# 2_cyber60-2-matrix.net
KiCad netlist of a schematic drawn in Altium Designer
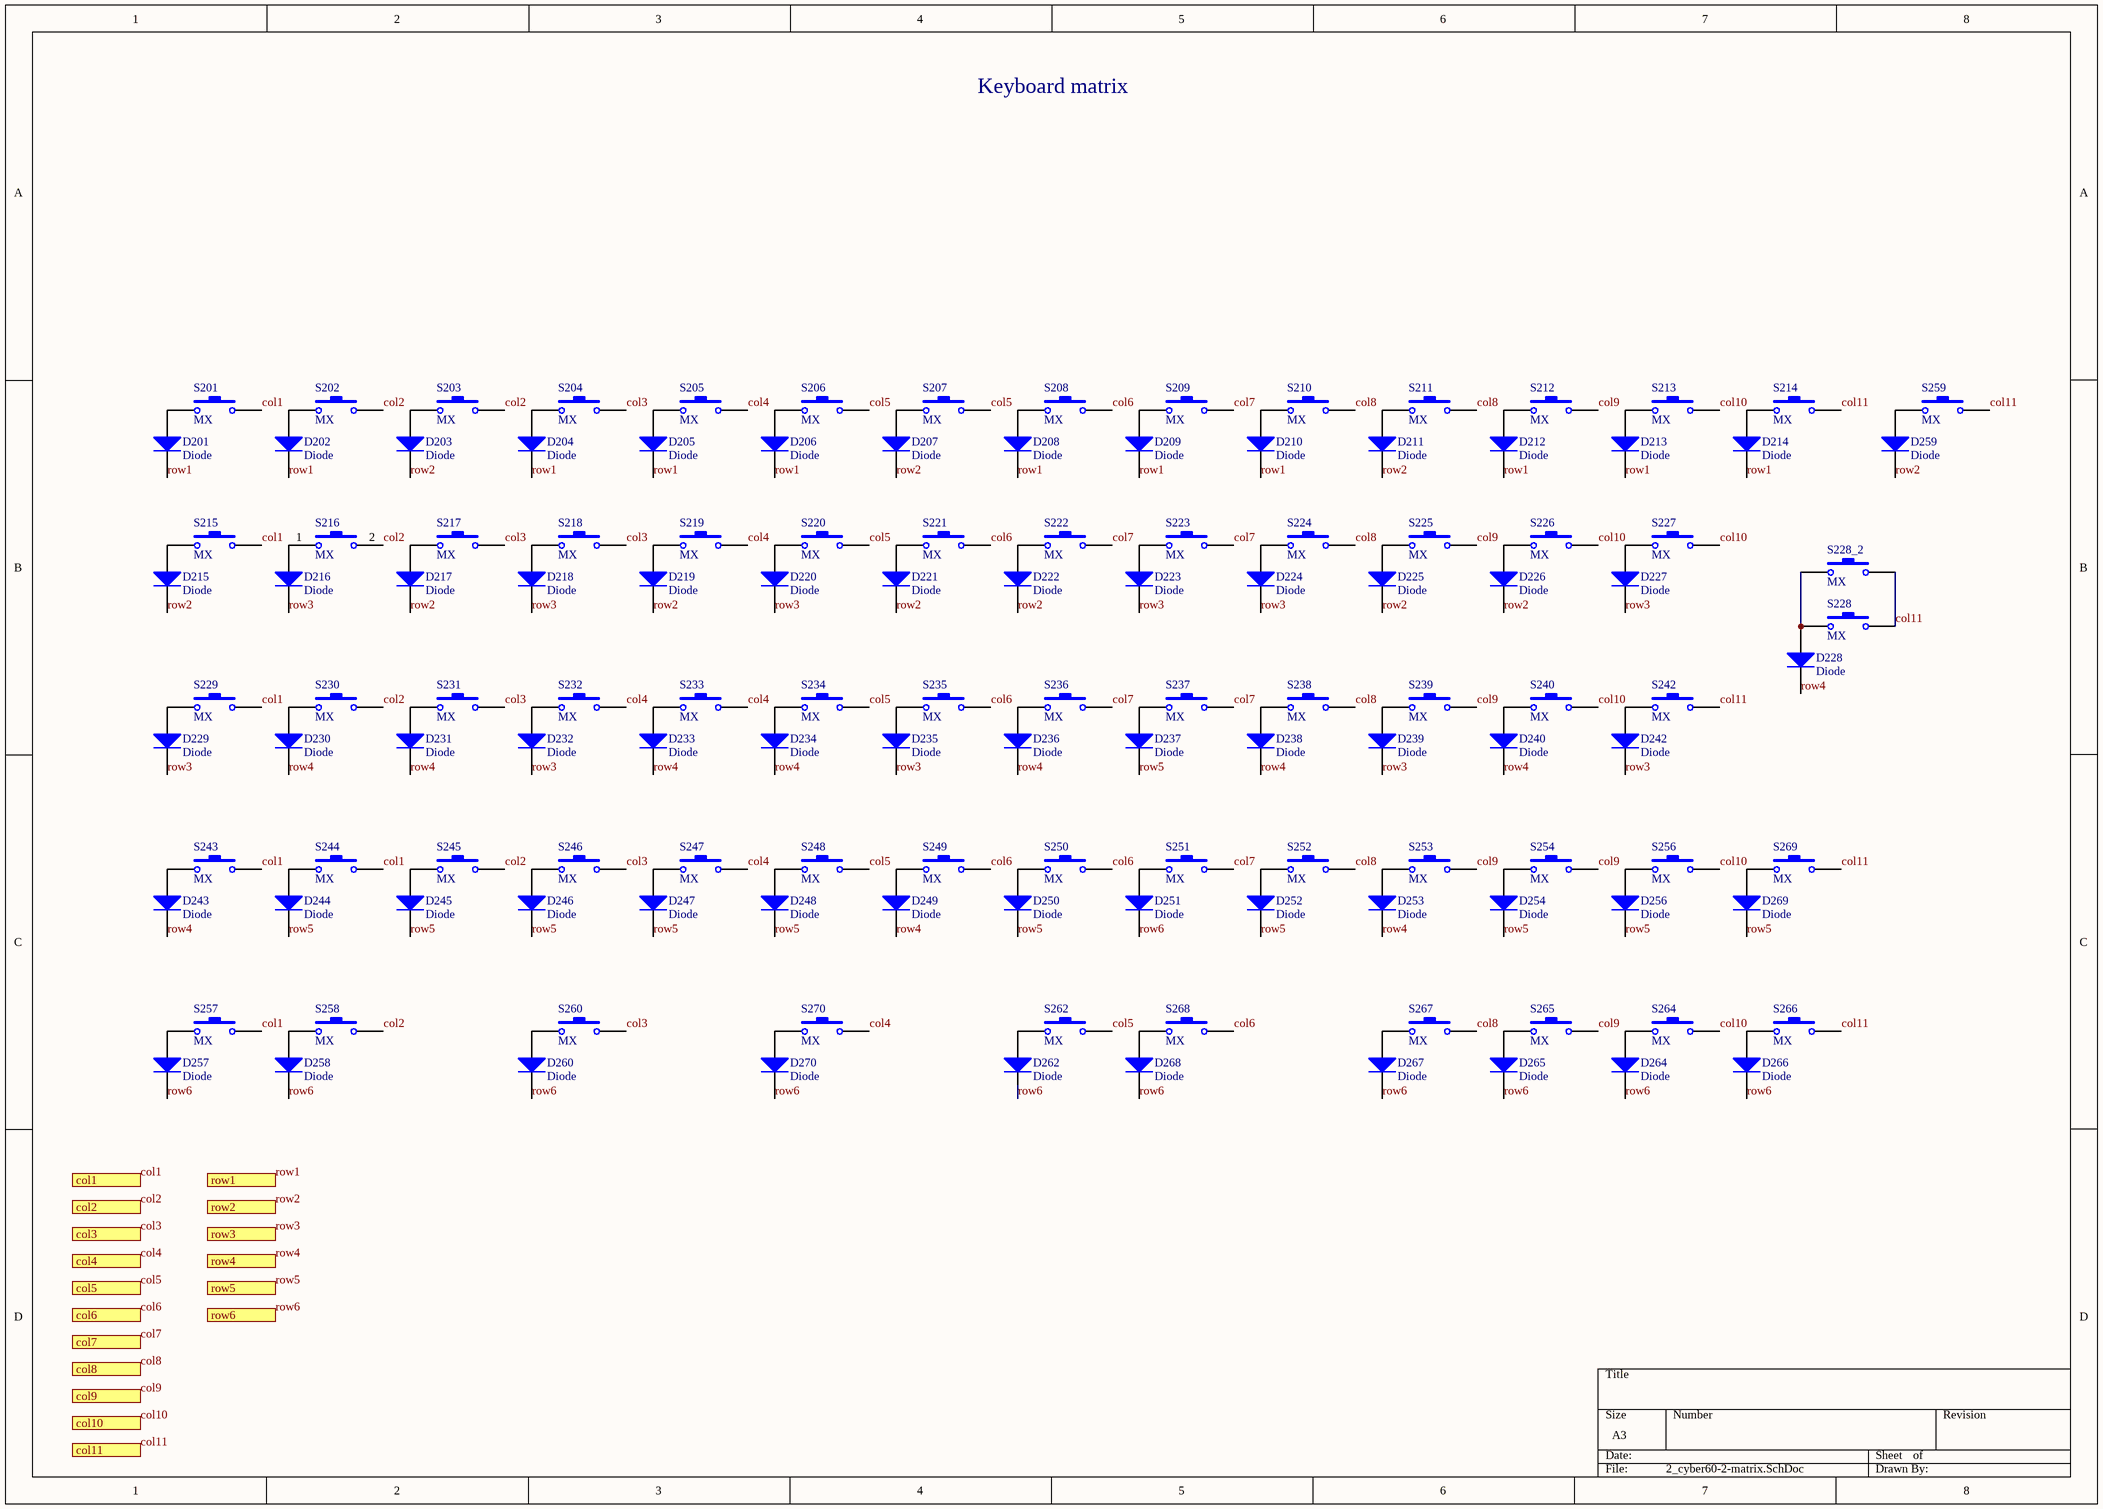
[diagram p0: 2_cyber60-2-matrix.SchDoc]

(export (version "E")
  (design (tool "Eeschema 10.0.6"))
  (components
    (comp (ref "D201")
      (value "Diode")
      (footprint "SOD-123")
      (description "Default Diode")
      (fields (field (name "LCSC PART #") "C81598") (field (name "MRF.PART") "1N4148W"))
      (libsource (lib "Miscellaneous Devices") (part "Diode"))
    )
    (comp (ref "D202")
      (value "Diode")
      (footprint "SOD-123")
      (description "Default Diode")
      (fields (field (name "LCSC PART #") "C81598") (field (name "MRF.PART") "1N4148W"))
      (libsource (lib "Miscellaneous Devices") (part "Diode"))
    )
    (comp (ref "D203")
      (value "Diode")
      (footprint "SOD-123")
      (description "Default Diode")
      (fields (field (name "LCSC PART #") "C81598") (field (name "MRF.PART") "1N4148W"))
      (libsource (lib "Miscellaneous Devices") (part "Diode"))
    )
    (comp (ref "D204")
      (value "Diode")
      (footprint "SOD-123")
      (description "Default Diode")
      (fields (field (name "LCSC PART #") "C81598") (field (name "MRF.PART") "1N4148W"))
      (libsource (lib "Miscellaneous Devices") (part "Diode"))
    )
    (comp (ref "D205")
      (value "Diode")
      (footprint "SOD-123")
      (description "Default Diode")
      (fields (field (name "LCSC PART #") "C81598") (field (name "MRF.PART") "1N4148W"))
      (libsource (lib "Miscellaneous Devices") (part "Diode"))
    )
    (comp (ref "D206")
      (value "Diode")
      (footprint "SOD-123")
      (description "Default Diode")
      (fields (field (name "LCSC PART #") "C81598") (field (name "MRF.PART") "1N4148W"))
      (libsource (lib "Miscellaneous Devices") (part "Diode"))
    )
    (comp (ref "D207")
      (value "Diode")
      (footprint "SOD-123")
      (description "Default Diode")
      (fields (field (name "LCSC PART #") "C81598") (field (name "MRF.PART") "1N4148W"))
      (libsource (lib "Miscellaneous Devices") (part "Diode"))
    )
    (comp (ref "D208")
      (value "Diode")
      (footprint "SOD-123")
      (description "Default Diode")
      (fields (field (name "LCSC PART #") "C81598") (field (name "MRF.PART") "1N4148W"))
      (libsource (lib "Miscellaneous Devices") (part "Diode"))
    )
    (comp (ref "D209")
      (value "Diode")
      (footprint "SOD-123")
      (description "Default Diode")
      (fields (field (name "LCSC PART #") "C81598") (field (name "MRF.PART") "1N4148W"))
      (libsource (lib "Miscellaneous Devices") (part "Diode"))
    )
    (comp (ref "D210")
      (value "Diode")
      (footprint "SOD-123")
      (description "Default Diode")
      (fields (field (name "LCSC PART #") "C81598") (field (name "MRF.PART") "1N4148W"))
      (libsource (lib "Miscellaneous Devices") (part "Diode"))
    )
    (comp (ref "D211")
      (value "Diode")
      (footprint "SOD-123")
      (description "Default Diode")
      (fields (field (name "LCSC PART #") "C81598") (field (name "MRF.PART") "1N4148W"))
      (libsource (lib "Miscellaneous Devices") (part "Diode"))
    )
    (comp (ref "D212")
      (value "Diode")
      (footprint "SOD-123")
      (description "Default Diode")
      (fields (field (name "LCSC PART #") "C81598") (field (name "MRF.PART") "1N4148W"))
      (libsource (lib "Miscellaneous Devices") (part "Diode"))
    )
    (comp (ref "D213")
      (value "Diode")
      (footprint "SOD-123")
      (description "Default Diode")
      (fields (field (name "LCSC PART #") "C81598") (field (name "MRF.PART") "1N4148W"))
      (libsource (lib "Miscellaneous Devices") (part "Diode"))
    )
    (comp (ref "D214")
      (value "Diode")
      (footprint "SOD-123")
      (description "Default Diode")
      (fields (field (name "LCSC PART #") "C81598") (field (name "MRF.PART") "1N4148W"))
      (libsource (lib "Miscellaneous Devices") (part "Diode"))
    )
    (comp (ref "D215")
      (value "Diode")
      (footprint "SOD-123")
      (description "Default Diode")
      (fields (field (name "LCSC PART #") "C81598") (field (name "MRF.PART") "1N4148W"))
      (libsource (lib "Miscellaneous Devices") (part "Diode"))
    )
    (comp (ref "D216")
      (value "Diode")
      (footprint "SOD-123")
      (description "Default Diode")
      (fields (field (name "LCSC PART #") "C81598") (field (name "MRF.PART") "1N4148W"))
      (libsource (lib "Miscellaneous Devices") (part "Diode"))
    )
    (comp (ref "D217")
      (value "Diode")
      (footprint "SOD-123")
      (description "Default Diode")
      (fields (field (name "LCSC PART #") "C81598") (field (name "MRF.PART") "1N4148W"))
      (libsource (lib "Miscellaneous Devices") (part "Diode"))
    )
    (comp (ref "D218")
      (value "Diode")
      (footprint "SOD-123")
      (description "Default Diode")
      (fields (field (name "LCSC PART #") "C81598") (field (name "MRF.PART") "1N4148W"))
      (libsource (lib "Miscellaneous Devices") (part "Diode"))
    )
    (comp (ref "D219")
      (value "Diode")
      (footprint "SOD-123")
      (description "Default Diode")
      (fields (field (name "LCSC PART #") "C81598") (field (name "MRF.PART") "1N4148W"))
      (libsource (lib "Miscellaneous Devices") (part "Diode"))
    )
    (comp (ref "D220")
      (value "Diode")
      (footprint "SOD-123")
      (description "Default Diode")
      (fields (field (name "LCSC PART #") "C81598") (field (name "MRF.PART") "1N4148W"))
      (libsource (lib "Miscellaneous Devices") (part "Diode"))
    )
    (comp (ref "D221")
      (value "Diode")
      (footprint "SOD-123")
      (description "Default Diode")
      (fields (field (name "LCSC PART #") "C81598") (field (name "MRF.PART") "1N4148W"))
      (libsource (lib "Miscellaneous Devices") (part "Diode"))
    )
    (comp (ref "D222")
      (value "Diode")
      (footprint "SOD-123")
      (description "Default Diode")
      (fields (field (name "LCSC PART #") "C81598") (field (name "MRF.PART") "1N4148W"))
      (libsource (lib "Miscellaneous Devices") (part "Diode"))
    )
    (comp (ref "D223")
      (value "Diode")
      (footprint "SOD-123")
      (description "Default Diode")
      (fields (field (name "LCSC PART #") "C81598") (field (name "MRF.PART") "1N4148W"))
      (libsource (lib "Miscellaneous Devices") (part "Diode"))
    )
    (comp (ref "D224")
      (value "Diode")
      (footprint "SOD-123")
      (description "Default Diode")
      (fields (field (name "LCSC PART #") "C81598") (field (name "MRF.PART") "1N4148W"))
      (libsource (lib "Miscellaneous Devices") (part "Diode"))
    )
    (comp (ref "D225")
      (value "Diode")
      (footprint "SOD-123")
      (description "Default Diode")
      (fields (field (name "LCSC PART #") "C81598") (field (name "MRF.PART") "1N4148W"))
      (libsource (lib "Miscellaneous Devices") (part "Diode"))
    )
    (comp (ref "D226")
      (value "Diode")
      (footprint "SOD-123")
      (description "Default Diode")
      (fields (field (name "LCSC PART #") "C81598") (field (name "MRF.PART") "1N4148W"))
      (libsource (lib "Miscellaneous Devices") (part "Diode"))
    )
    (comp (ref "D227")
      (value "Diode")
      (footprint "SOD-123")
      (description "Default Diode")
      (fields (field (name "LCSC PART #") "C81598") (field (name "MRF.PART") "1N4148W"))
      (libsource (lib "Miscellaneous Devices") (part "Diode"))
    )
    (comp (ref "D228")
      (value "Diode")
      (footprint "SOD-123")
      (description "Default Diode")
      (fields (field (name "LCSC PART #") "C81598") (field (name "MRF.PART") "1N4148W"))
      (libsource (lib "Miscellaneous Devices") (part "Diode"))
    )
    (comp (ref "D229")
      (value "Diode")
      (footprint "SOD-123")
      (description "Default Diode")
      (fields (field (name "LCSC PART #") "C81598") (field (name "MRF.PART") "1N4148W"))
      (libsource (lib "Miscellaneous Devices") (part "Diode"))
    )
    (comp (ref "D230")
      (value "Diode")
      (footprint "SOD-123")
      (description "Default Diode")
      (fields (field (name "LCSC PART #") "C81598") (field (name "MRF.PART") "1N4148W"))
      (libsource (lib "Miscellaneous Devices") (part "Diode"))
    )
    (comp (ref "D231")
      (value "Diode")
      (footprint "SOD-123")
      (description "Default Diode")
      (fields (field (name "LCSC PART #") "C81598") (field (name "MRF.PART") "1N4148W"))
      (libsource (lib "Miscellaneous Devices") (part "Diode"))
    )
    (comp (ref "D232")
      (value "Diode")
      (footprint "SOD-123")
      (description "Default Diode")
      (fields (field (name "LCSC PART #") "C81598") (field (name "MRF.PART") "1N4148W"))
      (libsource (lib "Miscellaneous Devices") (part "Diode"))
    )
    (comp (ref "D233")
      (value "Diode")
      (footprint "SOD-123")
      (description "Default Diode")
      (fields (field (name "LCSC PART #") "C81598") (field (name "MRF.PART") "1N4148W"))
      (libsource (lib "Miscellaneous Devices") (part "Diode"))
    )
    (comp (ref "D234")
      (value "Diode")
      (footprint "SOD-123")
      (description "Default Diode")
      (fields (field (name "LCSC PART #") "C81598") (field (name "MRF.PART") "1N4148W"))
      (libsource (lib "Miscellaneous Devices") (part "Diode"))
    )
    (comp (ref "D235")
      (value "Diode")
      (footprint "SOD-123")
      (description "Default Diode")
      (fields (field (name "LCSC PART #") "C81598") (field (name "MRF.PART") "1N4148W"))
      (libsource (lib "Miscellaneous Devices") (part "Diode"))
    )
    (comp (ref "D236")
      (value "Diode")
      (footprint "SOD-123")
      (description "Default Diode")
      (fields (field (name "LCSC PART #") "C81598") (field (name "MRF.PART") "1N4148W"))
      (libsource (lib "Miscellaneous Devices") (part "Diode"))
    )
    (comp (ref "D237")
      (value "Diode")
      (footprint "SOD-123")
      (description "Default Diode")
      (fields (field (name "LCSC PART #") "C81598") (field (name "MRF.PART") "1N4148W"))
      (libsource (lib "Miscellaneous Devices") (part "Diode"))
    )
    (comp (ref "D238")
      (value "Diode")
      (footprint "SOD-123")
      (description "Default Diode")
      (fields (field (name "LCSC PART #") "C81598") (field (name "MRF.PART") "1N4148W"))
      (libsource (lib "Miscellaneous Devices") (part "Diode"))
    )
    (comp (ref "D239")
      (value "Diode")
      (footprint "SOD-123")
      (description "Default Diode")
      (fields (field (name "LCSC PART #") "C81598") (field (name "MRF.PART") "1N4148W"))
      (libsource (lib "Miscellaneous Devices") (part "Diode"))
    )
    (comp (ref "D240")
      (value "Diode")
      (footprint "SOD-123")
      (description "Default Diode")
      (fields (field (name "LCSC PART #") "C81598") (field (name "MRF.PART") "1N4148W"))
      (libsource (lib "Miscellaneous Devices") (part "Diode"))
    )
    (comp (ref "D242")
      (value "Diode")
      (footprint "SOD-123")
      (description "Default Diode")
      (fields (field (name "LCSC PART #") "C81598") (field (name "MRF.PART") "1N4148W"))
      (libsource (lib "Miscellaneous Devices") (part "Diode"))
    )
    (comp (ref "D243")
      (value "Diode")
      (footprint "SOD-123")
      (description "Default Diode")
      (fields (field (name "LCSC PART #") "C81598") (field (name "MRF.PART") "1N4148W"))
      (libsource (lib "Miscellaneous Devices") (part "Diode"))
    )
    (comp (ref "D244")
      (value "Diode")
      (footprint "SOD-123")
      (description "Default Diode")
      (fields (field (name "LCSC PART #") "C81598") (field (name "MRF.PART") "1N4148W"))
      (libsource (lib "Miscellaneous Devices") (part "Diode"))
    )
    (comp (ref "D245")
      (value "Diode")
      (footprint "SOD-123")
      (description "Default Diode")
      (fields (field (name "LCSC PART #") "C81598") (field (name "MRF.PART") "1N4148W"))
      (libsource (lib "Miscellaneous Devices") (part "Diode"))
    )
    (comp (ref "D246")
      (value "Diode")
      (footprint "SOD-123")
      (description "Default Diode")
      (fields (field (name "LCSC PART #") "C81598") (field (name "MRF.PART") "1N4148W"))
      (libsource (lib "Miscellaneous Devices") (part "Diode"))
    )
    (comp (ref "D247")
      (value "Diode")
      (footprint "SOD-123")
      (description "Default Diode")
      (fields (field (name "LCSC PART #") "C81598") (field (name "MRF.PART") "1N4148W"))
      (libsource (lib "Miscellaneous Devices") (part "Diode"))
    )
    (comp (ref "D248")
      (value "Diode")
      (footprint "SOD-123")
      (description "Default Diode")
      (fields (field (name "LCSC PART #") "C81598") (field (name "MRF.PART") "1N4148W"))
      (libsource (lib "Miscellaneous Devices") (part "Diode"))
    )
    (comp (ref "D249")
      (value "Diode")
      (footprint "SOD-123")
      (description "Default Diode")
      (fields (field (name "LCSC PART #") "C81598") (field (name "MRF.PART") "1N4148W"))
      (libsource (lib "Miscellaneous Devices") (part "Diode"))
    )
    (comp (ref "D250")
      (value "Diode")
      (footprint "SOD-123")
      (description "Default Diode")
      (fields (field (name "LCSC PART #") "C81598") (field (name "MRF.PART") "1N4148W"))
      (libsource (lib "Miscellaneous Devices") (part "Diode"))
    )
    (comp (ref "D251")
      (value "Diode")
      (footprint "SOD-123")
      (description "Default Diode")
      (fields (field (name "LCSC PART #") "C81598") (field (name "MRF.PART") "1N4148W"))
      (libsource (lib "Miscellaneous Devices") (part "Diode"))
    )
    (comp (ref "D252")
      (value "Diode")
      (footprint "SOD-123")
      (description "Default Diode")
      (fields (field (name "LCSC PART #") "C81598") (field (name "MRF.PART") "1N4148W"))
      (libsource (lib "Miscellaneous Devices") (part "Diode"))
    )
    (comp (ref "D253")
      (value "Diode")
      (footprint "SOD-123")
      (description "Default Diode")
      (fields (field (name "LCSC PART #") "C81598") (field (name "MRF.PART") "1N4148W"))
      (libsource (lib "Miscellaneous Devices") (part "Diode"))
    )
    (comp (ref "D254")
      (value "Diode")
      (footprint "SOD-123")
      (description "Default Diode")
      (fields (field (name "LCSC PART #") "C81598") (field (name "MRF.PART") "1N4148W"))
      (libsource (lib "Miscellaneous Devices") (part "Diode"))
    )
    (comp (ref "D256")
      (value "Diode")
      (footprint "SOD-123")
      (description "Default Diode")
      (fields (field (name "LCSC PART #") "C81598") (field (name "MRF.PART") "1N4148W"))
      (libsource (lib "Miscellaneous Devices") (part "Diode"))
    )
    (comp (ref "D257")
      (value "Diode")
      (footprint "SOD-123")
      (description "Default Diode")
      (fields (field (name "LCSC PART #") "C81598") (field (name "MRF.PART") "1N4148W"))
      (libsource (lib "Miscellaneous Devices") (part "Diode"))
    )
    (comp (ref "D258")
      (value "Diode")
      (footprint "SOD-123")
      (description "Default Diode")
      (fields (field (name "LCSC PART #") "C81598") (field (name "MRF.PART") "1N4148W"))
      (libsource (lib "Miscellaneous Devices") (part "Diode"))
    )
    (comp (ref "D259")
      (value "Diode")
      (footprint "SOD-123")
      (description "Default Diode")
      (fields (field (name "LCSC PART #") "C81598") (field (name "MRF.PART") "1N4148W"))
      (libsource (lib "Miscellaneous Devices") (part "Diode"))
    )
    (comp (ref "D260")
      (value "Diode")
      (footprint "SOD-123")
      (description "Default Diode")
      (fields (field (name "LCSC PART #") "C81598") (field (name "MRF.PART") "1N4148W"))
      (libsource (lib "Miscellaneous Devices") (part "Diode"))
    )
    (comp (ref "D262")
      (value "Diode")
      (footprint "SOD-123")
      (description "Default Diode")
      (fields (field (name "LCSC PART #") "C81598") (field (name "MRF.PART") "1N4148W"))
      (libsource (lib "Miscellaneous Devices") (part "Diode"))
    )
    (comp (ref "D264")
      (value "Diode")
      (footprint "SOD-123")
      (description "Default Diode")
      (fields (field (name "LCSC PART #") "C81598") (field (name "MRF.PART") "1N4148W"))
      (libsource (lib "Miscellaneous Devices") (part "Diode"))
    )
    (comp (ref "D265")
      (value "Diode")
      (footprint "SOD-123")
      (description "Default Diode")
      (fields (field (name "LCSC PART #") "C81598") (field (name "MRF.PART") "1N4148W"))
      (libsource (lib "Miscellaneous Devices") (part "Diode"))
    )
    (comp (ref "D266")
      (value "Diode")
      (footprint "SOD-123")
      (description "Default Diode")
      (fields (field (name "LCSC PART #") "C81598") (field (name "MRF.PART") "1N4148W"))
      (libsource (lib "Miscellaneous Devices") (part "Diode"))
    )
    (comp (ref "D267")
      (value "Diode")
      (footprint "SOD-123")
      (description "Default Diode")
      (fields (field (name "LCSC PART #") "C81598") (field (name "MRF.PART") "1N4148W"))
      (libsource (lib "Miscellaneous Devices") (part "Diode"))
    )
    (comp (ref "D268")
      (value "Diode")
      (footprint "SOD-123")
      (description "Default Diode")
      (fields (field (name "LCSC PART #") "C81598") (field (name "MRF.PART") "1N4148W"))
      (libsource (lib "Miscellaneous Devices") (part "Diode"))
    )
    (comp (ref "D269")
      (value "Diode")
      (footprint "SOD-123")
      (description "Default Diode")
      (fields (field (name "LCSC PART #") "C81598") (field (name "MRF.PART") "1N4148W"))
      (libsource (lib "Miscellaneous Devices") (part "Diode"))
    )
    (comp (ref "D270")
      (value "Diode")
      (footprint "SOD-123")
      (description "Default Diode")
      (fields (field (name "LCSC PART #") "C81598") (field (name "MRF.PART") "1N4148W"))
      (libsource (lib "Miscellaneous Devices") (part "Diode"))
    )
    (comp (ref "S201")
      (value "MX")
      (footprint "MX-switch - switched pol")
      (description "Switch")
      (libsource (lib "Miscellaneous Devices") (part "SW-PB"))
    )
    (comp (ref "S202")
      (value "MX")
      (footprint "MX-switch - switched pol - connector")
      (description "Switch")
      (libsource (lib "Miscellaneous Devices") (part "SW-PB"))
    )
    (comp (ref "S203")
      (value "MX")
      (footprint "MX-switch - switched pol")
      (description "Switch")
      (libsource (lib "Miscellaneous Devices") (part "SW-PB"))
    )
    (comp (ref "S204")
      (value "MX")
      (footprint "MX-switch")
      (description "Switch")
      (libsource (lib "Miscellaneous Devices") (part "SW-PB"))
    )
    (comp (ref "S205")
      (value "MX")
      (footprint "MX-switch - switched pol")
      (description "Switch")
      (libsource (lib "Miscellaneous Devices") (part "SW-PB"))
    )
    (comp (ref "S206")
      (value "MX")
      (footprint "MX-switch - switched pol")
      (description "Switch")
      (libsource (lib "Miscellaneous Devices") (part "SW-PB"))
    )
    (comp (ref "S207")
      (value "MX")
      (footprint "MX-switch - switched pol")
      (description "Switch")
      (libsource (lib "Miscellaneous Devices") (part "SW-PB"))
    )
    (comp (ref "S208")
      (value "MX")
      (footprint "MX-switch - switched pol")
      (description "Switch")
      (libsource (lib "Miscellaneous Devices") (part "SW-PB"))
    )
    (comp (ref "S209")
      (value "MX")
      (footprint "MX-switch - switched pol")
      (description "Switch")
      (libsource (lib "Miscellaneous Devices") (part "SW-PB"))
    )
    (comp (ref "S210")
      (value "MX")
      (footprint "MX-switch - switched pol")
      (description "Switch")
      (libsource (lib "Miscellaneous Devices") (part "SW-PB"))
    )
    (comp (ref "S211")
      (value "MX")
      (footprint "MX-switch - switched pol")
      (description "Switch")
      (libsource (lib "Miscellaneous Devices") (part "SW-PB"))
    )
    (comp (ref "S212")
      (value "MX")
      (footprint "MX-switch - switched pol")
      (description "Switch")
      (libsource (lib "Miscellaneous Devices") (part "SW-PB"))
    )
    (comp (ref "S213")
      (value "MX")
      (footprint "MX-switch - switched pol")
      (description "Switch")
      (libsource (lib "Miscellaneous Devices") (part "SW-PB"))
    )
    (comp (ref "S214")
      (value "MX")
      (footprint "MX-switch - switched pol")
      (description "Switch")
      (libsource (lib "Miscellaneous Devices") (part "SW-PB"))
    )
    (comp (ref "S215")
      (value "MX")
      (footprint "MX-switch - 1.5U - switched pol")
      (description "TAB")
      (libsource (lib "Miscellaneous Devices") (part "SW-PB"))
    )
    (comp (ref "S216")
      (value "MX")
      (footprint "MX-switch - switched pol")
      (description "Switch")
      (libsource (lib "") (part "SW-PB_1"))
    )
    (comp (ref "S217")
      (value "MX")
      (footprint "MX-switch - switched pol")
      (description "Switch")
      (libsource (lib "Miscellaneous Devices") (part "SW-PB"))
    )
    (comp (ref "S218")
      (value "MX")
      (footprint "MX-switch - switched pol")
      (description "Switch")
      (libsource (lib "Miscellaneous Devices") (part "SW-PB"))
    )
    (comp (ref "S219")
      (value "MX")
      (footprint "MX-switch - switched pol")
      (description "Switch")
      (libsource (lib "Miscellaneous Devices") (part "SW-PB"))
    )
    (comp (ref "S220")
      (value "MX")
      (footprint "MX-switch")
      (description "Switch")
      (libsource (lib "Miscellaneous Devices") (part "SW-PB"))
    )
    (comp (ref "S221")
      (value "MX")
      (footprint "MX-switch - switched pol")
      (description "Switch")
      (libsource (lib "Miscellaneous Devices") (part "SW-PB"))
    )
    (comp (ref "S222")
      (value "MX")
      (footprint "MX-switch - switched pol")
      (description "Switch")
      (libsource (lib "Miscellaneous Devices") (part "SW-PB"))
    )
    (comp (ref "S223")
      (value "MX")
      (footprint "MX-switch - switched pol")
      (description "Switch")
      (libsource (lib "Miscellaneous Devices") (part "SW-PB"))
    )
    (comp (ref "S224")
      (value "MX")
      (footprint "MX-switch - switched pol")
      (description "Switch")
      (libsource (lib "Miscellaneous Devices") (part "SW-PB"))
    )
    (comp (ref "S225")
      (value "MX")
      (footprint "MX-switch - switched pol")
      (description "Switch")
      (libsource (lib "Miscellaneous Devices") (part "SW-PB"))
    )
    (comp (ref "S226")
      (value "MX")
      (footprint "MX-switch")
      (description "Switch")
      (libsource (lib "Miscellaneous Devices") (part "SW-PB"))
    )
    (comp (ref "S227")
      (value "MX")
      (footprint "MX-switch")
      (description "Switch")
      (libsource (lib "Miscellaneous Devices") (part "SW-PB"))
    )
    (comp (ref "S228")
      (value "MX")
      (footprint "MX-switch - 1.5U")
      (description "Switch")
      (libsource (lib "Miscellaneous Devices") (part "SW-PB"))
    )
    (comp (ref "S228_2")
      (value "MX")
      (footprint "MX-switch")
      (description "Switch")
      (libsource (lib "Miscellaneous Devices") (part "SW-PB"))
    )
    (comp (ref "S229")
      (value "MX")
      (footprint "MX-switch - CAPS")
      (description "Switch")
      (libsource (lib "Miscellaneous Devices") (part "SW-PB"))
    )
    (comp (ref "S230")
      (value "MX")
      (footprint "MX-switch - switched pol")
      (description "Switch")
      (libsource (lib "Miscellaneous Devices") (part "SW-PB"))
    )
    (comp (ref "S231")
      (value "MX")
      (footprint "MX-switch - switched pol")
      (description "Switch")
      (libsource (lib "Miscellaneous Devices") (part "SW-PB"))
    )
    (comp (ref "S232")
      (value "MX")
      (footprint "MX-switch - switched pol")
      (description "Switch")
      (libsource (lib "Miscellaneous Devices") (part "SW-PB"))
    )
    (comp (ref "S233")
      (value "MX")
      (footprint "MX-switch - switched pol")
      (description "Switch")
      (libsource (lib "Miscellaneous Devices") (part "SW-PB"))
    )
    (comp (ref "S234")
      (value "MX")
      (footprint "MX-switch")
      (description "Switch")
      (libsource (lib "Miscellaneous Devices") (part "SW-PB"))
    )
    (comp (ref "S235")
      (value "MX")
      (footprint "MX-switch - switched pol")
      (description "Switch")
      (libsource (lib "Miscellaneous Devices") (part "SW-PB"))
    )
    (comp (ref "S236")
      (value "MX")
      (footprint "MX-switch - switched pol")
      (description "Switch")
      (libsource (lib "Miscellaneous Devices") (part "SW-PB"))
    )
    (comp (ref "S237")
      (value "MX")
      (footprint "MX-switch - switched pol")
      (description "Switch")
      (libsource (lib "Miscellaneous Devices") (part "SW-PB"))
    )
    (comp (ref "S238")
      (value "MX")
      (footprint "MX-switch - switched pol")
      (description "Switch")
      (libsource (lib "Miscellaneous Devices") (part "SW-PB"))
    )
    (comp (ref "S239")
      (value "MX")
      (footprint "MX-switch")
      (description "Switch")
      (libsource (lib "Miscellaneous Devices") (part "SW-PB"))
    )
    (comp (ref "S240")
      (value "MX")
      (footprint "MX-switch - switched pol")
      (description "Switch")
      (libsource (lib "Miscellaneous Devices") (part "SW-PB"))
    )
    (comp (ref "S242")
      (value "MX")
      (footprint "MX-switch - Enter")
      (description "Switch")
      (libsource (lib "Miscellaneous Devices") (part "SW-PB"))
    )
    (comp (ref "S243")
      (value "MX")
      (footprint "MX-switch - Left shift")
      (description "Switch")
      (libsource (lib "Miscellaneous Devices") (part "SW-PB"))
    )
    (comp (ref "S244")
      (value "MX")
      (footprint "MX-switch - switched pol")
      (description "Switch")
      (libsource (lib "Miscellaneous Devices") (part "SW-PB"))
    )
    (comp (ref "S245")
      (value "MX")
      (footprint "MX-switch - switched pol")
      (description "Switch")
      (libsource (lib "Miscellaneous Devices") (part "SW-PB"))
    )
    (comp (ref "S246")
      (value "MX")
      (footprint "MX-switch - switched pol")
      (description "Switch")
      (libsource (lib "Miscellaneous Devices") (part "SW-PB"))
    )
    (comp (ref "S247")
      (value "MX")
      (footprint "MX-switch - switched pol")
      (description "Switch")
      (libsource (lib "Miscellaneous Devices") (part "SW-PB"))
    )
    (comp (ref "S248")
      (value "MX")
      (footprint "MX-switch")
      (description "Switch")
      (libsource (lib "Miscellaneous Devices") (part "SW-PB"))
    )
    (comp (ref "S249")
      (value "MX")
      (footprint "MX-switch - switched pol")
      (description "Switch")
      (libsource (lib "Miscellaneous Devices") (part "SW-PB"))
    )
    (comp (ref "S250")
      (value "MX")
      (footprint "MX-switch - switched pol")
      (description "Switch")
      (libsource (lib "Miscellaneous Devices") (part "SW-PB"))
    )
    (comp (ref "S251")
      (value "MX")
      (footprint "MX-switch - switched pol")
      (description "Switch")
      (libsource (lib "Miscellaneous Devices") (part "SW-PB"))
    )
    (comp (ref "S252")
      (value "MX")
      (footprint "MX-switch - switched pol")
      (description "Switch")
      (libsource (lib "Miscellaneous Devices") (part "SW-PB"))
    )
    (comp (ref "S253")
      (value "MX")
      (footprint "MX-switch - switched pol")
      (description "Switch")
      (libsource (lib "Miscellaneous Devices") (part "SW-PB"))
    )
    (comp (ref "S254")
      (value "MX")
      (footprint "MX-switch - switched pol")
      (description "Switch")
      (libsource (lib "Miscellaneous Devices") (part "SW-PB"))
    )
    (comp (ref "S256")
      (value "MX")
      (footprint "MX-switch - right shift")
      (description "Switch")
      (libsource (lib "Miscellaneous Devices") (part "SW-PB"))
    )
    (comp (ref "S257")
      (value "MX")
      (footprint "MX-switch - 1.5u MOD-L")
      (description "Switch")
      (libsource (lib "Miscellaneous Devices") (part "SW-PB"))
    )
    (comp (ref "S258")
      (value "MX")
      (footprint "MX-switch - 1u MOD-L")
      (description "Switch")
      (libsource (lib "Miscellaneous Devices") (part "SW-PB"))
    )
    (comp (ref "S259")
      (value "MX")
      (footprint "MX-switch - backspace")
      (description "Switch")
      (libsource (lib "Miscellaneous Devices") (part "SW-PB"))
    )
    (comp (ref "S260")
      (value "MX")
      (footprint "MX-switch - 1.5u MOD-L")
      (description "Switch")
      (libsource (lib "Miscellaneous Devices") (part "SW-PB"))
    )
    (comp (ref "S262")
      (value "MX")
      (footprint "MX-switch - Space_V3")
      (description "Switch")
      (libsource (lib "Miscellaneous Devices") (part "SW-PB"))
    )
    (comp (ref "S264")
      (value "MX")
      (footprint "MX-switch - 1u MOD-R")
      (description "Switch")
      (libsource (lib "Miscellaneous Devices") (part "SW-PB"))
    )
    (comp (ref "S265")
      (value "MX")
      (footprint "MX-switch - 1.5u MOD-R")
      (description "Switch")
      (libsource (lib "Miscellaneous Devices") (part "SW-PB"))
    )
    (comp (ref "S266")
      (value "MX")
      (footprint "MX-switch - 1.5u MOD-R")
      (description "Switch")
      (libsource (lib "Miscellaneous Devices") (part "SW-PB"))
    )
    (comp (ref "S267")
      (value "MX")
      (footprint "MX-switch - switched pol")
      (description "Switch")
      (libsource (lib "Miscellaneous Devices") (part "SW-PB"))
    )
    (comp (ref "S268")
      (value "MX")
      (footprint "MX-switch - R split space_V2")
      (description "Switch")
      (libsource (lib "Miscellaneous Devices") (part "SW-PB"))
    )
    (comp (ref "S269")
      (value "MX")
      (footprint "MX-switch")
      (description "Switch")
      (libsource (lib "Miscellaneous Devices") (part "SW-PB"))
    )
    (comp (ref "S270")
      (value "MX")
      (footprint "MX-switch - L split space_V2")
      (description "Switch")
      (libsource (lib "Miscellaneous Devices") (part "SW-PB"))
    )
  )
  (nets
    (net (code "1") (name "/col1") (class "Default")
      (node (ref "S201") (pin "2") (pinfunction "2_2") (pintype "passive"))
      (node (ref "S215") (pin "2") (pinfunction "2_2") (pintype "passive"))
      (node (ref "S229") (pin "2") (pinfunction "2_2") (pintype "passive"))
      (node (ref "S243") (pin "2") (pinfunction "2_2") (pintype "passive"))
      (node (ref "S244") (pin "2") (pinfunction "2_2") (pintype "passive"))
      (node (ref "S257") (pin "2") (pinfunction "2_2") (pintype "passive"))
    )
    (net (code "2") (name "/col2") (class "Default")
      (node (ref "S202") (pin "2") (pinfunction "2_2") (pintype "passive"))
      (node (ref "S203") (pin "2") (pinfunction "2_2") (pintype "passive"))
      (node (ref "S216") (pin "2") (pinfunction "2_2") (pintype "passive"))
      (node (ref "S230") (pin "2") (pinfunction "2_2") (pintype "passive"))
      (node (ref "S245") (pin "2") (pinfunction "2_2") (pintype "passive"))
      (node (ref "S258") (pin "2") (pinfunction "2_2") (pintype "passive"))
    )
    (net (code "3") (name "/col3") (class "Default")
      (node (ref "S204") (pin "2") (pinfunction "2_2") (pintype "passive"))
      (node (ref "S217") (pin "2") (pinfunction "2_2") (pintype "passive"))
      (node (ref "S218") (pin "2") (pinfunction "2_2") (pintype "passive"))
      (node (ref "S231") (pin "2") (pinfunction "2_2") (pintype "passive"))
      (node (ref "S246") (pin "2") (pinfunction "2_2") (pintype "passive"))
      (node (ref "S260") (pin "2") (pinfunction "2_2") (pintype "passive"))
    )
    (net (code "4") (name "/col4") (class "Default")
      (node (ref "S205") (pin "2") (pinfunction "2_2") (pintype "passive"))
      (node (ref "S219") (pin "2") (pinfunction "2_2") (pintype "passive"))
      (node (ref "S232") (pin "2") (pinfunction "2_2") (pintype "passive"))
      (node (ref "S233") (pin "2") (pinfunction "2_2") (pintype "passive"))
      (node (ref "S247") (pin "2") (pinfunction "2_2") (pintype "passive"))
      (node (ref "S270") (pin "2") (pinfunction "2_2") (pintype "passive"))
    )
    (net (code "5") (name "/col5") (class "Default")
      (node (ref "S206") (pin "2") (pinfunction "2_2") (pintype "passive"))
      (node (ref "S207") (pin "2") (pinfunction "2_2") (pintype "passive"))
      (node (ref "S220") (pin "2") (pinfunction "2_2") (pintype "passive"))
      (node (ref "S234") (pin "2") (pinfunction "2_2") (pintype "passive"))
      (node (ref "S248") (pin "2") (pinfunction "2_2") (pintype "passive"))
      (node (ref "S262") (pin "1") (pinfunction "1_1") (pintype "passive"))
    )
    (net (code "6") (name "/col6") (class "Default")
      (node (ref "S208") (pin "2") (pinfunction "2_2") (pintype "passive"))
      (node (ref "S221") (pin "2") (pinfunction "2_2") (pintype "passive"))
      (node (ref "S235") (pin "2") (pinfunction "2_2") (pintype "passive"))
      (node (ref "S249") (pin "2") (pinfunction "2_2") (pintype "passive"))
      (node (ref "S250") (pin "2") (pinfunction "2_2") (pintype "passive"))
      (node (ref "S268") (pin "2") (pinfunction "2_2") (pintype "passive"))
    )
    (net (code "7") (name "/col7") (class "Default")
      (node (ref "S209") (pin "2") (pinfunction "2_2") (pintype "passive"))
      (node (ref "S222") (pin "2") (pinfunction "2_2") (pintype "passive"))
      (node (ref "S223") (pin "2") (pinfunction "2_2") (pintype "passive"))
      (node (ref "S236") (pin "2") (pinfunction "2_2") (pintype "passive"))
      (node (ref "S237") (pin "2") (pinfunction "2_2") (pintype "passive"))
      (node (ref "S251") (pin "2") (pinfunction "2_2") (pintype "passive"))
    )
    (net (code "8") (name "/col8") (class "Default")
      (node (ref "S210") (pin "2") (pinfunction "2_2") (pintype "passive"))
      (node (ref "S211") (pin "2") (pinfunction "2_2") (pintype "passive"))
      (node (ref "S224") (pin "2") (pinfunction "2_2") (pintype "passive"))
      (node (ref "S238") (pin "2") (pinfunction "2_2") (pintype "passive"))
      (node (ref "S252") (pin "2") (pinfunction "2_2") (pintype "passive"))
      (node (ref "S267") (pin "2") (pinfunction "2_2") (pintype "passive"))
    )
    (net (code "9") (name "/col9") (class "Default")
      (node (ref "S212") (pin "2") (pinfunction "2_2") (pintype "passive"))
      (node (ref "S225") (pin "2") (pinfunction "2_2") (pintype "passive"))
      (node (ref "S239") (pin "2") (pinfunction "2_2") (pintype "passive"))
      (node (ref "S253") (pin "2") (pinfunction "2_2") (pintype "passive"))
      (node (ref "S254") (pin "2") (pinfunction "2_2") (pintype "passive"))
      (node (ref "S265") (pin "1") (pinfunction "1_1") (pintype "passive"))
    )
    (net (code "10") (name "/col10") (class "Default")
      (node (ref "S213") (pin "2") (pinfunction "2_2") (pintype "passive"))
      (node (ref "S226") (pin "2") (pinfunction "2_2") (pintype "passive"))
      (node (ref "S227") (pin "2") (pinfunction "2_2") (pintype "passive"))
      (node (ref "S240") (pin "2") (pinfunction "2_2") (pintype "passive"))
      (node (ref "S256") (pin "2") (pinfunction "2_2") (pintype "passive"))
      (node (ref "S264") (pin "2") (pinfunction "2_2") (pintype "passive"))
    )
    (net (code "11") (name "/col11") (class "Default")
      (node (ref "S214") (pin "2") (pinfunction "2_2") (pintype "passive"))
      (node (ref "S228") (pin "2") (pinfunction "2_2") (pintype "passive"))
      (node (ref "S228_2") (pin "2") (pinfunction "2_2") (pintype "passive"))
      (node (ref "S242") (pin "2") (pinfunction "2_2") (pintype "passive"))
      (node (ref "S259") (pin "2") (pinfunction "2_2") (pintype "passive"))
      (node (ref "S266") (pin "2") (pinfunction "2_2") (pintype "passive"))
      (node (ref "S269") (pin "2") (pinfunction "2_2") (pintype "passive"))
    )
    (net (code "12") (name "/row1") (class "Default")
      (node (ref "D201") (pin "2") (pinfunction "K_2") (pintype "passive"))
      (node (ref "D202") (pin "2") (pinfunction "K_2") (pintype "passive"))
      (node (ref "D204") (pin "2") (pinfunction "K_2") (pintype "passive"))
      (node (ref "D205") (pin "2") (pinfunction "K_2") (pintype "passive"))
      (node (ref "D206") (pin "2") (pinfunction "K_2") (pintype "passive"))
      (node (ref "D208") (pin "2") (pinfunction "K_2") (pintype "passive"))
      (node (ref "D209") (pin "2") (pinfunction "K_2") (pintype "passive"))
      (node (ref "D210") (pin "2") (pinfunction "K_2") (pintype "passive"))
      (node (ref "D212") (pin "2") (pinfunction "K_2") (pintype "passive"))
      (node (ref "D213") (pin "2") (pinfunction "K_2") (pintype "passive"))
      (node (ref "D214") (pin "2") (pinfunction "K_2") (pintype "passive"))
    )
    (net (code "13") (name "/row2") (class "Default")
      (node (ref "D203") (pin "2") (pinfunction "K_2") (pintype "passive"))
      (node (ref "D207") (pin "2") (pinfunction "K_2") (pintype "passive"))
      (node (ref "D211") (pin "2") (pinfunction "K_2") (pintype "passive"))
      (node (ref "D215") (pin "2") (pinfunction "K_2") (pintype "passive"))
      (node (ref "D217") (pin "2") (pinfunction "K_2") (pintype "passive"))
      (node (ref "D219") (pin "2") (pinfunction "K_2") (pintype "passive"))
      (node (ref "D221") (pin "2") (pinfunction "K_2") (pintype "passive"))
      (node (ref "D222") (pin "2") (pinfunction "K_2") (pintype "passive"))
      (node (ref "D225") (pin "2") (pinfunction "K_2") (pintype "passive"))
      (node (ref "D226") (pin "2") (pinfunction "K_2") (pintype "passive"))
      (node (ref "D259") (pin "2") (pinfunction "K_2") (pintype "passive"))
    )
    (net (code "14") (name "/row3") (class "Default")
      (node (ref "D216") (pin "2") (pinfunction "K_2") (pintype "passive"))
      (node (ref "D218") (pin "2") (pinfunction "K_2") (pintype "passive"))
      (node (ref "D220") (pin "2") (pinfunction "K_2") (pintype "passive"))
      (node (ref "D223") (pin "2") (pinfunction "K_2") (pintype "passive"))
      (node (ref "D224") (pin "2") (pinfunction "K_2") (pintype "passive"))
      (node (ref "D227") (pin "2") (pinfunction "K_2") (pintype "passive"))
      (node (ref "D229") (pin "2") (pinfunction "K_2") (pintype "passive"))
      (node (ref "D232") (pin "2") (pinfunction "K_2") (pintype "passive"))
      (node (ref "D235") (pin "2") (pinfunction "K_2") (pintype "passive"))
      (node (ref "D239") (pin "2") (pinfunction "K_2") (pintype "passive"))
      (node (ref "D242") (pin "2") (pinfunction "K_2") (pintype "passive"))
    )
    (net (code "15") (name "/row4") (class "Default")
      (node (ref "D228") (pin "2") (pinfunction "K_2") (pintype "passive"))
      (node (ref "D230") (pin "2") (pinfunction "K_2") (pintype "passive"))
      (node (ref "D231") (pin "2") (pinfunction "K_2") (pintype "passive"))
      (node (ref "D233") (pin "2") (pinfunction "K_2") (pintype "passive"))
      (node (ref "D234") (pin "2") (pinfunction "K_2") (pintype "passive"))
      (node (ref "D236") (pin "2") (pinfunction "K_2") (pintype "passive"))
      (node (ref "D238") (pin "2") (pinfunction "K_2") (pintype "passive"))
      (node (ref "D240") (pin "2") (pinfunction "K_2") (pintype "passive"))
      (node (ref "D243") (pin "2") (pinfunction "K_2") (pintype "passive"))
      (node (ref "D249") (pin "2") (pinfunction "K_2") (pintype "passive"))
      (node (ref "D253") (pin "2") (pinfunction "K_2") (pintype "passive"))
    )
    (net (code "16") (name "/row5") (class "Default")
      (node (ref "D237") (pin "2") (pinfunction "K_2") (pintype "passive"))
      (node (ref "D244") (pin "2") (pinfunction "K_2") (pintype "passive"))
      (node (ref "D245") (pin "2") (pinfunction "K_2") (pintype "passive"))
      (node (ref "D246") (pin "2") (pinfunction "K_2") (pintype "passive"))
      (node (ref "D247") (pin "2") (pinfunction "K_2") (pintype "passive"))
      (node (ref "D248") (pin "2") (pinfunction "K_2") (pintype "passive"))
      (node (ref "D250") (pin "2") (pinfunction "K_2") (pintype "passive"))
      (node (ref "D252") (pin "2") (pinfunction "K_2") (pintype "passive"))
      (node (ref "D254") (pin "2") (pinfunction "K_2") (pintype "passive"))
      (node (ref "D256") (pin "2") (pinfunction "K_2") (pintype "passive"))
      (node (ref "D269") (pin "2") (pinfunction "K_2") (pintype "passive"))
    )
    (net (code "17") (name "/row6") (class "Default")
      (node (ref "D251") (pin "2") (pinfunction "K_2") (pintype "passive"))
      (node (ref "D257") (pin "2") (pinfunction "K_2") (pintype "passive"))
      (node (ref "D258") (pin "2") (pinfunction "K_2") (pintype "passive"))
      (node (ref "D260") (pin "2") (pinfunction "K_2") (pintype "passive"))
      (node (ref "D262") (pin "2") (pinfunction "K_2") (pintype "passive"))
      (node (ref "D264") (pin "2") (pinfunction "K_2") (pintype "passive"))
      (node (ref "D265") (pin "2") (pinfunction "K_2") (pintype "passive"))
      (node (ref "D266") (pin "2") (pinfunction "K_2") (pintype "passive"))
      (node (ref "D267") (pin "2") (pinfunction "K_2") (pintype "passive"))
      (node (ref "D268") (pin "2") (pinfunction "K_2") (pintype "passive"))
      (node (ref "D270") (pin "2") (pinfunction "K_2") (pintype "passive"))
    )
    (net (code "18") (name "Net-(D201-A)") (class "Default")
      (node (ref "D201") (pin "1") (pinfunction "A_1") (pintype "passive"))
      (node (ref "S201") (pin "1") (pinfunction "1_1") (pintype "passive"))
    )
    (net (code "19") (name "Net-(D202-A)") (class "Default")
      (node (ref "D202") (pin "1") (pinfunction "A_1") (pintype "passive"))
      (node (ref "S202") (pin "1") (pinfunction "1_1") (pintype "passive"))
    )
    (net (code "20") (name "Net-(D203-A)") (class "Default")
      (node (ref "D203") (pin "1") (pinfunction "A_1") (pintype "passive"))
      (node (ref "S203") (pin "1") (pinfunction "1_1") (pintype "passive"))
    )
    (net (code "21") (name "Net-(D204-A)") (class "Default")
      (node (ref "D204") (pin "1") (pinfunction "A_1") (pintype "passive"))
      (node (ref "S204") (pin "1") (pinfunction "1_1") (pintype "passive"))
    )
    (net (code "22") (name "Net-(D205-A)") (class "Default")
      (node (ref "D205") (pin "1") (pinfunction "A_1") (pintype "passive"))
      (node (ref "S205") (pin "1") (pinfunction "1_1") (pintype "passive"))
    )
    (net (code "23") (name "Net-(D206-A)") (class "Default")
      (node (ref "D206") (pin "1") (pinfunction "A_1") (pintype "passive"))
      (node (ref "S206") (pin "1") (pinfunction "1_1") (pintype "passive"))
    )
    (net (code "24") (name "Net-(D207-A)") (class "Default")
      (node (ref "D207") (pin "1") (pinfunction "A_1") (pintype "passive"))
      (node (ref "S207") (pin "1") (pinfunction "1_1") (pintype "passive"))
    )
    (net (code "25") (name "Net-(D208-A)") (class "Default")
      (node (ref "D208") (pin "1") (pinfunction "A_1") (pintype "passive"))
      (node (ref "S208") (pin "1") (pinfunction "1_1") (pintype "passive"))
    )
    (net (code "26") (name "Net-(D209-A)") (class "Default")
      (node (ref "D209") (pin "1") (pinfunction "A_1") (pintype "passive"))
      (node (ref "S209") (pin "1") (pinfunction "1_1") (pintype "passive"))
    )
    (net (code "27") (name "Net-(D210-A)") (class "Default")
      (node (ref "D210") (pin "1") (pinfunction "A_1") (pintype "passive"))
      (node (ref "S210") (pin "1") (pinfunction "1_1") (pintype "passive"))
    )
    (net (code "28") (name "Net-(D211-A)") (class "Default")
      (node (ref "D211") (pin "1") (pinfunction "A_1") (pintype "passive"))
      (node (ref "S211") (pin "1") (pinfunction "1_1") (pintype "passive"))
    )
    (net (code "29") (name "Net-(D212-A)") (class "Default")
      (node (ref "D212") (pin "1") (pinfunction "A_1") (pintype "passive"))
      (node (ref "S212") (pin "1") (pinfunction "1_1") (pintype "passive"))
    )
    (net (code "30") (name "Net-(D213-A)") (class "Default")
      (node (ref "D213") (pin "1") (pinfunction "A_1") (pintype "passive"))
      (node (ref "S213") (pin "1") (pinfunction "1_1") (pintype "passive"))
    )
    (net (code "31") (name "Net-(D214-A)") (class "Default")
      (node (ref "D214") (pin "1") (pinfunction "A_1") (pintype "passive"))
      (node (ref "S214") (pin "1") (pinfunction "1_1") (pintype "passive"))
    )
    (net (code "32") (name "Net-(D215-A)") (class "Default")
      (node (ref "D215") (pin "1") (pinfunction "A_1") (pintype "passive"))
      (node (ref "S215") (pin "1") (pinfunction "1_1") (pintype "passive"))
    )
    (net (code "33") (name "Net-(D216-A)") (class "Default")
      (node (ref "D216") (pin "1") (pinfunction "A_1") (pintype "passive"))
      (node (ref "S216") (pin "1") (pinfunction "1_1") (pintype "passive"))
    )
    (net (code "34") (name "Net-(D217-A)") (class "Default")
      (node (ref "D217") (pin "1") (pinfunction "A_1") (pintype "passive"))
      (node (ref "S217") (pin "1") (pinfunction "1_1") (pintype "passive"))
    )
    (net (code "35") (name "Net-(D218-A)") (class "Default")
      (node (ref "D218") (pin "1") (pinfunction "A_1") (pintype "passive"))
      (node (ref "S218") (pin "1") (pinfunction "1_1") (pintype "passive"))
    )
    (net (code "36") (name "Net-(D219-A)") (class "Default")
      (node (ref "D219") (pin "1") (pinfunction "A_1") (pintype "passive"))
      (node (ref "S219") (pin "1") (pinfunction "1_1") (pintype "passive"))
    )
    (net (code "37") (name "Net-(D220-A)") (class "Default")
      (node (ref "D220") (pin "1") (pinfunction "A_1") (pintype "passive"))
      (node (ref "S220") (pin "1") (pinfunction "1_1") (pintype "passive"))
    )
    (net (code "38") (name "Net-(D221-A)") (class "Default")
      (node (ref "D221") (pin "1") (pinfunction "A_1") (pintype "passive"))
      (node (ref "S221") (pin "1") (pinfunction "1_1") (pintype "passive"))
    )
    (net (code "39") (name "Net-(D222-A)") (class "Default")
      (node (ref "D222") (pin "1") (pinfunction "A_1") (pintype "passive"))
      (node (ref "S222") (pin "1") (pinfunction "1_1") (pintype "passive"))
    )
    (net (code "40") (name "Net-(D223-A)") (class "Default")
      (node (ref "D223") (pin "1") (pinfunction "A_1") (pintype "passive"))
      (node (ref "S223") (pin "1") (pinfunction "1_1") (pintype "passive"))
    )
    (net (code "41") (name "Net-(D224-A)") (class "Default")
      (node (ref "D224") (pin "1") (pinfunction "A_1") (pintype "passive"))
      (node (ref "S224") (pin "1") (pinfunction "1_1") (pintype "passive"))
    )
    (net (code "42") (name "Net-(D225-A)") (class "Default")
      (node (ref "D225") (pin "1") (pinfunction "A_1") (pintype "passive"))
      (node (ref "S225") (pin "1") (pinfunction "1_1") (pintype "passive"))
    )
    (net (code "43") (name "Net-(D226-A)") (class "Default")
      (node (ref "D226") (pin "1") (pinfunction "A_1") (pintype "passive"))
      (node (ref "S226") (pin "1") (pinfunction "1_1") (pintype "passive"))
    )
    (net (code "44") (name "Net-(D227-A)") (class "Default")
      (node (ref "D227") (pin "1") (pinfunction "A_1") (pintype "passive"))
      (node (ref "S227") (pin "1") (pinfunction "1_1") (pintype "passive"))
    )
    (net (code "45") (name "Net-(D228-A)") (class "Default")
      (node (ref "D228") (pin "1") (pinfunction "A_1") (pintype "passive"))
      (node (ref "S228") (pin "1") (pinfunction "1_1") (pintype "passive"))
      (node (ref "S228_2") (pin "1") (pinfunction "1_1") (pintype "passive"))
    )
    (net (code "46") (name "Net-(D229-A)") (class "Default")
      (node (ref "D229") (pin "1") (pinfunction "A_1") (pintype "passive"))
      (node (ref "S229") (pin "1") (pinfunction "1_1") (pintype "passive"))
    )
    (net (code "47") (name "Net-(D230-A)") (class "Default")
      (node (ref "D230") (pin "1") (pinfunction "A_1") (pintype "passive"))
      (node (ref "S230") (pin "1") (pinfunction "1_1") (pintype "passive"))
    )
    (net (code "48") (name "Net-(D231-A)") (class "Default")
      (node (ref "D231") (pin "1") (pinfunction "A_1") (pintype "passive"))
      (node (ref "S231") (pin "1") (pinfunction "1_1") (pintype "passive"))
    )
    (net (code "49") (name "Net-(D232-A)") (class "Default")
      (node (ref "D232") (pin "1") (pinfunction "A_1") (pintype "passive"))
      (node (ref "S232") (pin "1") (pinfunction "1_1") (pintype "passive"))
    )
    (net (code "50") (name "Net-(D233-A)") (class "Default")
      (node (ref "D233") (pin "1") (pinfunction "A_1") (pintype "passive"))
      (node (ref "S233") (pin "1") (pinfunction "1_1") (pintype "passive"))
    )
    (net (code "51") (name "Net-(D234-A)") (class "Default")
      (node (ref "D234") (pin "1") (pinfunction "A_1") (pintype "passive"))
      (node (ref "S234") (pin "1") (pinfunction "1_1") (pintype "passive"))
    )
    (net (code "52") (name "Net-(D235-A)") (class "Default")
      (node (ref "D235") (pin "1") (pinfunction "A_1") (pintype "passive"))
      (node (ref "S235") (pin "1") (pinfunction "1_1") (pintype "passive"))
    )
    (net (code "53") (name "Net-(D236-A)") (class "Default")
      (node (ref "D236") (pin "1") (pinfunction "A_1") (pintype "passive"))
      (node (ref "S236") (pin "1") (pinfunction "1_1") (pintype "passive"))
    )
    (net (code "54") (name "Net-(D237-A)") (class "Default")
      (node (ref "D237") (pin "1") (pinfunction "A_1") (pintype "passive"))
      (node (ref "S237") (pin "1") (pinfunction "1_1") (pintype "passive"))
    )
    (net (code "55") (name "Net-(D238-A)") (class "Default")
      (node (ref "D238") (pin "1") (pinfunction "A_1") (pintype "passive"))
      (node (ref "S238") (pin "1") (pinfunction "1_1") (pintype "passive"))
    )
    (net (code "56") (name "Net-(D239-A)") (class "Default")
      (node (ref "D239") (pin "1") (pinfunction "A_1") (pintype "passive"))
      (node (ref "S239") (pin "1") (pinfunction "1_1") (pintype "passive"))
    )
    (net (code "57") (name "Net-(D240-A)") (class "Default")
      (node (ref "D240") (pin "1") (pinfunction "A_1") (pintype "passive"))
      (node (ref "S240") (pin "1") (pinfunction "1_1") (pintype "passive"))
    )
    (net (code "58") (name "Net-(D242-A)") (class "Default")
      (node (ref "D242") (pin "1") (pinfunction "A_1") (pintype "passive"))
      (node (ref "S242") (pin "1") (pinfunction "1_1") (pintype "passive"))
    )
    (net (code "59") (name "Net-(D243-A)") (class "Default")
      (node (ref "D243") (pin "1") (pinfunction "A_1") (pintype "passive"))
      (node (ref "S243") (pin "1") (pinfunction "1_1") (pintype "passive"))
    )
    (net (code "60") (name "Net-(D244-A)") (class "Default")
      (node (ref "D244") (pin "1") (pinfunction "A_1") (pintype "passive"))
      (node (ref "S244") (pin "1") (pinfunction "1_1") (pintype "passive"))
    )
    (net (code "61") (name "Net-(D245-A)") (class "Default")
      (node (ref "D245") (pin "1") (pinfunction "A_1") (pintype "passive"))
      (node (ref "S245") (pin "1") (pinfunction "1_1") (pintype "passive"))
    )
    (net (code "62") (name "Net-(D246-A)") (class "Default")
      (node (ref "D246") (pin "1") (pinfunction "A_1") (pintype "passive"))
      (node (ref "S246") (pin "1") (pinfunction "1_1") (pintype "passive"))
    )
    (net (code "63") (name "Net-(D247-A)") (class "Default")
      (node (ref "D247") (pin "1") (pinfunction "A_1") (pintype "passive"))
      (node (ref "S247") (pin "1") (pinfunction "1_1") (pintype "passive"))
    )
    (net (code "64") (name "Net-(D248-A)") (class "Default")
      (node (ref "D248") (pin "1") (pinfunction "A_1") (pintype "passive"))
      (node (ref "S248") (pin "1") (pinfunction "1_1") (pintype "passive"))
    )
    (net (code "65") (name "Net-(D249-A)") (class "Default")
      (node (ref "D249") (pin "1") (pinfunction "A_1") (pintype "passive"))
      (node (ref "S249") (pin "1") (pinfunction "1_1") (pintype "passive"))
    )
    (net (code "66") (name "Net-(D250-A)") (class "Default")
      (node (ref "D250") (pin "1") (pinfunction "A_1") (pintype "passive"))
      (node (ref "S250") (pin "1") (pinfunction "1_1") (pintype "passive"))
    )
    (net (code "67") (name "Net-(D251-A)") (class "Default")
      (node (ref "D251") (pin "1") (pinfunction "A_1") (pintype "passive"))
      (node (ref "S251") (pin "1") (pinfunction "1_1") (pintype "passive"))
    )
    (net (code "68") (name "Net-(D252-A)") (class "Default")
      (node (ref "D252") (pin "1") (pinfunction "A_1") (pintype "passive"))
      (node (ref "S252") (pin "1") (pinfunction "1_1") (pintype "passive"))
    )
    (net (code "69") (name "Net-(D253-A)") (class "Default")
      (node (ref "D253") (pin "1") (pinfunction "A_1") (pintype "passive"))
      (node (ref "S253") (pin "1") (pinfunction "1_1") (pintype "passive"))
    )
    (net (code "70") (name "Net-(D254-A)") (class "Default")
      (node (ref "D254") (pin "1") (pinfunction "A_1") (pintype "passive"))
      (node (ref "S254") (pin "1") (pinfunction "1_1") (pintype "passive"))
    )
    (net (code "71") (name "Net-(D256-A)") (class "Default")
      (node (ref "D256") (pin "1") (pinfunction "A_1") (pintype "passive"))
      (node (ref "S256") (pin "1") (pinfunction "1_1") (pintype "passive"))
    )
    (net (code "72") (name "Net-(D257-A)") (class "Default")
      (node (ref "D257") (pin "1") (pinfunction "A_1") (pintype "passive"))
      (node (ref "S257") (pin "1") (pinfunction "1_1") (pintype "passive"))
    )
    (net (code "73") (name "Net-(D258-A)") (class "Default")
      (node (ref "D258") (pin "1") (pinfunction "A_1") (pintype "passive"))
      (node (ref "S258") (pin "1") (pinfunction "1_1") (pintype "passive"))
    )
    (net (code "74") (name "Net-(D259-A)") (class "Default")
      (node (ref "D259") (pin "1") (pinfunction "A_1") (pintype "passive"))
      (node (ref "S259") (pin "1") (pinfunction "1_1") (pintype "passive"))
    )
    (net (code "75") (name "Net-(D260-A)") (class "Default")
      (node (ref "D260") (pin "1") (pinfunction "A_1") (pintype "passive"))
      (node (ref "S260") (pin "1") (pinfunction "1_1") (pintype "passive"))
    )
    (net (code "76") (name "Net-(D262-A)") (class "Default")
      (node (ref "D262") (pin "1") (pinfunction "A_1") (pintype "passive"))
      (node (ref "S262") (pin "2") (pinfunction "2_2") (pintype "passive"))
    )
    (net (code "77") (name "Net-(D264-A)") (class "Default")
      (node (ref "D264") (pin "1") (pinfunction "A_1") (pintype "passive"))
      (node (ref "S264") (pin "1") (pinfunction "1_1") (pintype "passive"))
    )
    (net (code "78") (name "Net-(D265-A)") (class "Default")
      (node (ref "D265") (pin "1") (pinfunction "A_1") (pintype "passive"))
      (node (ref "S265") (pin "2") (pinfunction "2_2") (pintype "passive"))
    )
    (net (code "79") (name "Net-(D266-A)") (class "Default")
      (node (ref "D266") (pin "1") (pinfunction "A_1") (pintype "passive"))
      (node (ref "S266") (pin "1") (pinfunction "1_1") (pintype "passive"))
    )
    (net (code "80") (name "Net-(D267-A)") (class "Default")
      (node (ref "D267") (pin "1") (pinfunction "A_1") (pintype "passive"))
      (node (ref "S267") (pin "1") (pinfunction "1_1") (pintype "passive"))
    )
    (net (code "81") (name "Net-(D268-A)") (class "Default")
      (node (ref "D268") (pin "1") (pinfunction "A_1") (pintype "passive"))
      (node (ref "S268") (pin "1") (pinfunction "1_1") (pintype "passive"))
    )
    (net (code "82") (name "Net-(D269-A)") (class "Default")
      (node (ref "D269") (pin "1") (pinfunction "A_1") (pintype "passive"))
      (node (ref "S269") (pin "1") (pinfunction "1_1") (pintype "passive"))
    )
    (net (code "83") (name "Net-(D270-A)") (class "Default")
      (node (ref "D270") (pin "1") (pinfunction "A_1") (pintype "passive"))
      (node (ref "S270") (pin "1") (pinfunction "1_1") (pintype "passive"))
    )
  )
)
